# Test.net
KiCad netlist of a schematic drawn in EAGLE
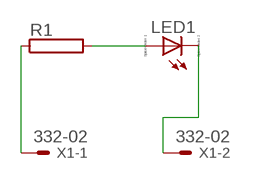
[diagram p0: schematic, sheet 1]

(export (version "E")
  (design (tool "Eeschema 10.0.6"))
  (components
    (comp (ref "LED1")
      (value "LED_ELD260")
      (footprint "eagle-import:LED_LD260")
      (libsource (lib "eagle-import") (part "LED_ELD260"))
    )
    (comp (ref "R1")
      (value "RAC01")
      (footprint "eagle-import:AC01")
      (libsource (lib "eagle-import") (part "RAC01"))
    )
    (comp (ref "X1")
      (value "332-02")
      (footprint "eagle-import:332-02")
      (libsource (lib "eagle-import") (part "332-02"))
    )
  )
  (nets
    (net (code "1") (name "Net-(LED1-C)") (class "Default")
      (node (ref "LED1") (pin "K") (pinfunction "C_K") (pintype "passive"))
      (node (ref "X1") (pin "2") (pinfunction "S_2") (pintype "passive"))
    )
    (net (code "2") (name "Net-(LED1-PadA)") (class "Default")
      (node (ref "LED1") (pin "A") (pinfunction "A_A") (pintype "passive"))
      (node (ref "R1") (pin "2") (pinfunction "2_2") (pintype "passive"))
    )
    (net (code "3") (name "Net-(X1A-S)") (class "Default")
      (node (ref "R1") (pin "1") (pinfunction "1_1") (pintype "passive"))
      (node (ref "X1") (pin "1") (pinfunction "S_1") (pintype "passive"))
    )
  )
)
